# ESP32.net
KiCad netlist of a schematic drawn in EAGLE
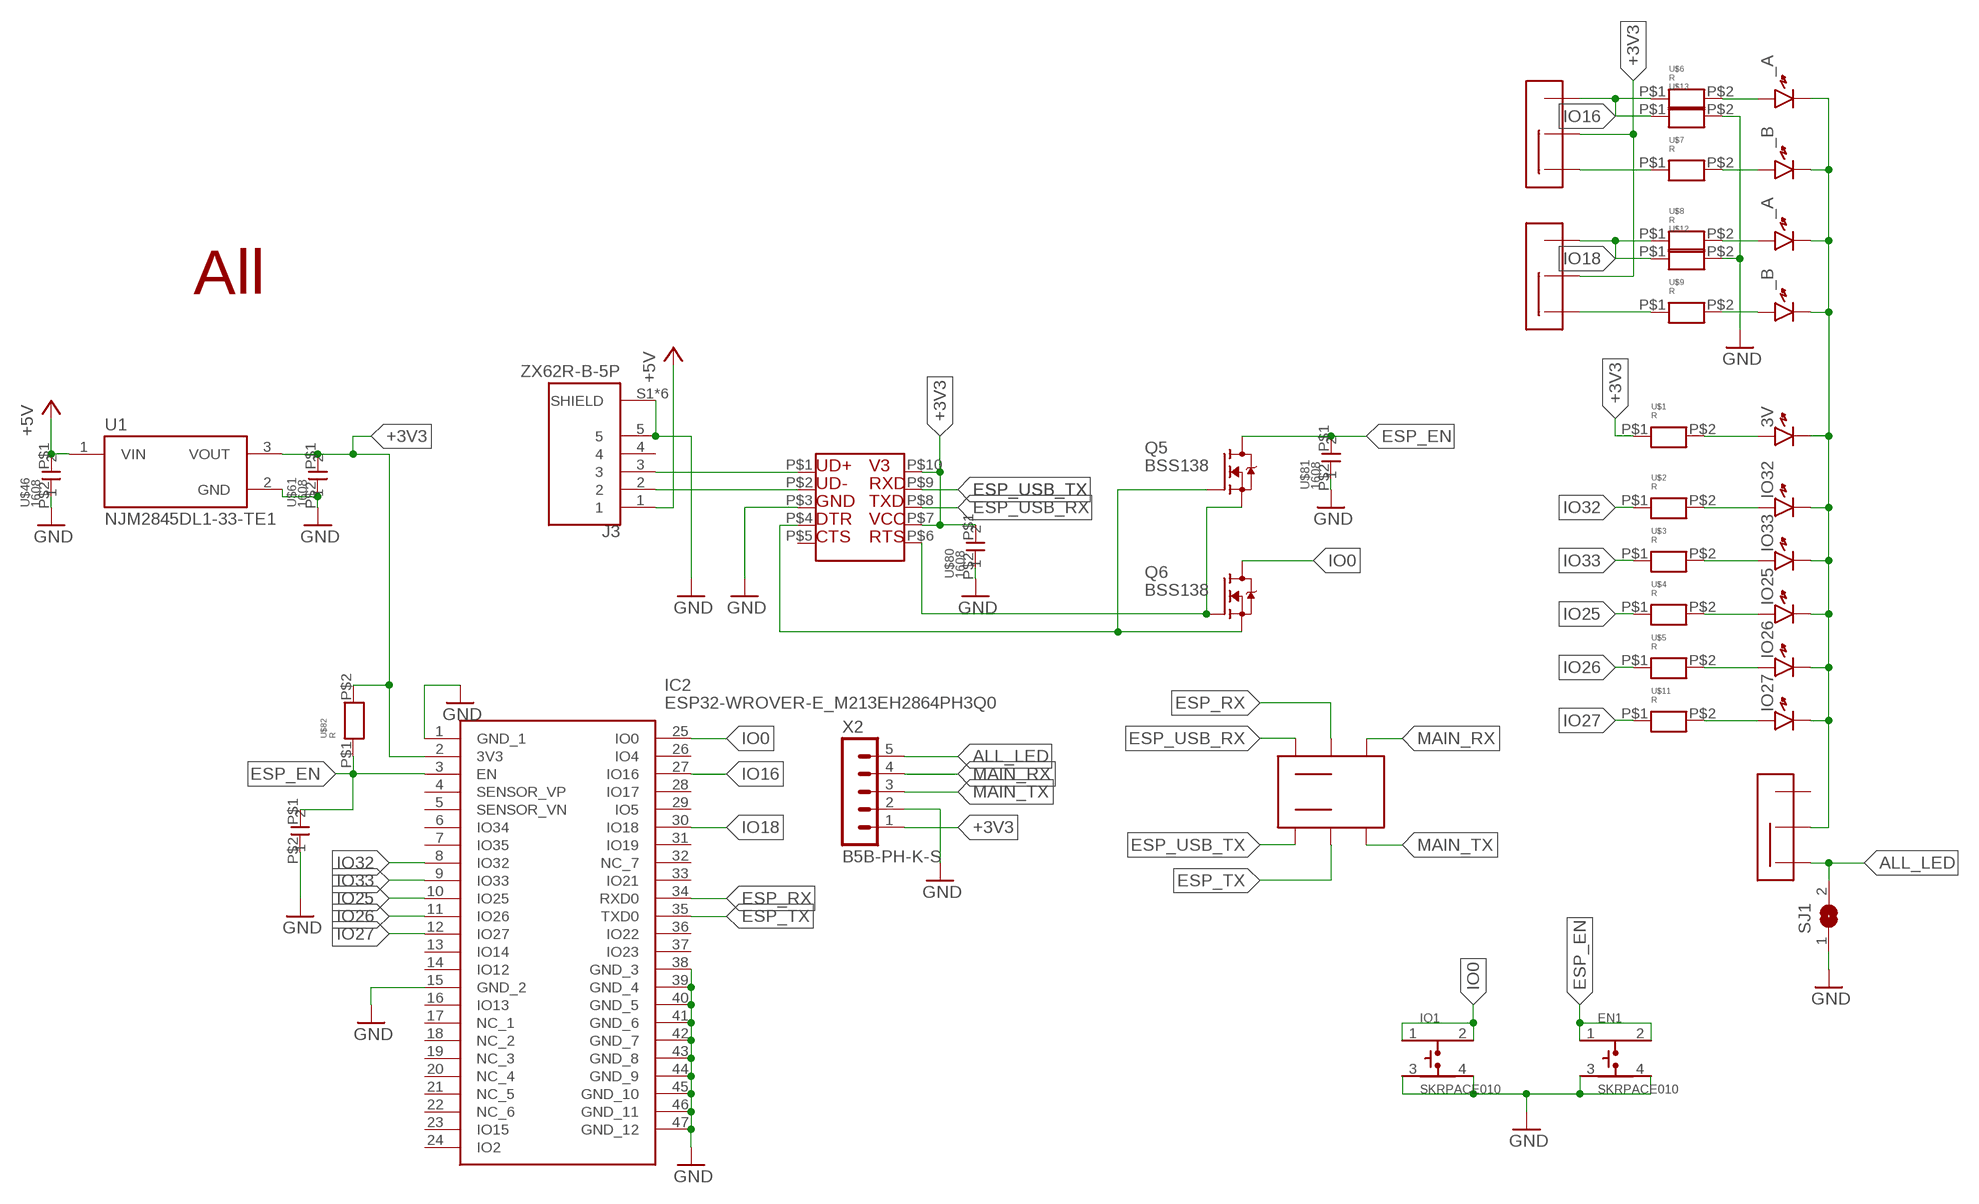
[diagram p0: schematic, sheet 1]

(export (version "E")
  (design (tool "Eeschema 10.0.6"))
  (components
    (comp (ref "3V")
      (value "LED1608")
      (footprint "eagle-import:LED1608")
      (libsource (lib "eagle-import") (part "LED1608"))
    )
    (comp (ref "EN1")
      (value "SKRPACE010")
      (footprint "eagle-import:SW_SKRPACE010")
      (fields (field (name "MF") "ALPS"))
      (libsource (lib "eagle-import") (part "SKRPACE010"))
    )
    (comp (ref "IC2")
      (value "ESP32-WROVER-E_M213EH2864PH3Q0")
      (footprint "eagle-import:ESP32WROVEREM213EH2864PH3Q0")
      (fields
        (field (name "MANUFACTURER_PART_NUMBER") "ESP32-WROVER-E(M213EH2864PH3Q0)")
        (field (name "MOUSER_PART_NUMBER") "356-ESP32WRVE22864PC")
      )
      (libsource (lib "eagle-import") (part "ESP32-WROVER-E_M213EH2864PH3Q0"))
    )
    (comp (ref "IO1")
      (value "SKRPACE010")
      (footprint "eagle-import:SW_SKRPACE010")
      (fields (field (name "MF") "ALPS"))
      (libsource (lib "eagle-import") (part "SKRPACE010"))
    )
    (comp (ref "IO25")
      (value "LED1608")
      (footprint "eagle-import:LED1608")
      (libsource (lib "eagle-import") (part "LED1608"))
    )
    (comp (ref "IO26")
      (value "LED1608")
      (footprint "eagle-import:LED1608")
      (libsource (lib "eagle-import") (part "LED1608"))
    )
    (comp (ref "IO27")
      (value "LED1608")
      (footprint "eagle-import:LED1608")
      (libsource (lib "eagle-import") (part "LED1608"))
    )
    (comp (ref "IO32")
      (value "LED1608")
      (footprint "eagle-import:LED1608")
      (libsource (lib "eagle-import") (part "LED1608"))
    )
    (comp (ref "IO33")
      (value "LED1608")
      (footprint "eagle-import:LED1608")
      (libsource (lib "eagle-import") (part "LED1608"))
    )
    (comp (ref "J3")
      (value "ZX62R-B-5P")
      (footprint "eagle-import:HRS_ZX62R-B-5P")
      (fields (field (name "MF") "Hirose"))
      (libsource (lib "eagle-import") (part "ZX62R-B-5P"))
    )
    (comp (ref "Q5")
      (value "BSS138")
      (footprint "eagle-import:SOT23")
      (fields (field (name "MF") "Fairchild"))
      (libsource (lib "eagle-import") (part "BSS138"))
    )
    (comp (ref "Q6")
      (value "BSS138")
      (footprint "eagle-import:SOT23")
      (fields (field (name "MF") "Fairchild"))
      (libsource (lib "eagle-import") (part "BSS138"))
    )
    (comp (ref "SJ1") (value "SJ") (footprint "eagle-import:SJ") (libsource (lib "eagle-import") (part "SJ")))
    (comp (ref "U$1") (value "R") (footprint "eagle-import:1608") (libsource (lib "eagle-import") (part "R")))
    (comp (ref "U$2") (value "R") (footprint "eagle-import:1608") (libsource (lib "eagle-import") (part "R")))
    (comp (ref "U$3") (value "R") (footprint "eagle-import:1608") (libsource (lib "eagle-import") (part "R")))
    (comp (ref "U$4") (value "R") (footprint "eagle-import:1608") (libsource (lib "eagle-import") (part "R")))
    (comp (ref "U$5") (value "R") (footprint "eagle-import:1608") (libsource (lib "eagle-import") (part "R")))
    (comp (ref "U$6") (value "R") (footprint "eagle-import:1608") (libsource (lib "eagle-import") (part "R")))
    (comp (ref "U$7") (value "R") (footprint "eagle-import:1608") (libsource (lib "eagle-import") (part "R")))
    (comp (ref "U$8") (value "R") (footprint "eagle-import:1608") (libsource (lib "eagle-import") (part "R")))
    (comp (ref "U$9") (value "R") (footprint "eagle-import:1608") (libsource (lib "eagle-import") (part "R")))
    (comp (ref "U$10")
      (value "SSW")
      (footprint "eagle-import:SSW")
      (libsource (lib "eagle-import") (part "SSW"))
    )
    (comp (ref "U$11")
      (value "R")
      (footprint "eagle-import:1608")
      (libsource (lib "eagle-import") (part "R"))
    )
    (comp (ref "U$12")
      (value "R")
      (footprint "eagle-import:1608")
      (libsource (lib "eagle-import") (part "R"))
    )
    (comp (ref "U$13")
      (value "R")
      (footprint "eagle-import:1608")
      (libsource (lib "eagle-import") (part "R"))
    )
    (comp (ref "U$14")
      (value "ALL")
      (footprint "eagle-import:ALL")
      (libsource (lib "eagle-import") (part "ALL"))
    )
    (comp (ref "U$46")
      (value "1608")
      (footprint "eagle-import:CON")
      (libsource (lib "eagle-import") (part "1608"))
    )
    (comp (ref "U$61")
      (value "1608")
      (footprint "eagle-import:CON")
      (libsource (lib "eagle-import") (part "1608"))
    )
    (comp (ref "U$79")
      (value "CH340K")
      (footprint "eagle-import:CH340K")
      (libsource (lib "eagle-import") (part "CH340K"))
    )
    (comp (ref "U$80")
      (value "1608")
      (footprint "eagle-import:CON")
      (libsource (lib "eagle-import") (part "1608"))
    )
    (comp (ref "U$81")
      (value "1608")
      (footprint "eagle-import:CON")
      (libsource (lib "eagle-import") (part "1608"))
    )
    (comp (ref "U$82")
      (value "R")
      (footprint "eagle-import:1608")
      (libsource (lib "eagle-import") (part "R"))
    )
    (comp (ref "U$83")
      (value "1608")
      (footprint "eagle-import:CON")
      (libsource (lib "eagle-import") (part "1608"))
    )
    (comp (ref "U$84")
      (value "2SW")
      (footprint "eagle-import:2SW")
      (libsource (lib "eagle-import") (part "2SW"))
    )
    (comp (ref "U$89")
      (value "SSW")
      (footprint "eagle-import:SSW")
      (libsource (lib "eagle-import") (part "SSW"))
    )
    (comp (ref "U$90")
      (value "SSW")
      (footprint "eagle-import:SSW")
      (libsource (lib "eagle-import") (part "SSW"))
    )
    (comp (ref "U1")
      (value "NJM2845DL1-33-TE1")
      (footprint "eagle-import:DPAK228P968X238-4N")
      (fields (field (name "MF") "NJR Corporation/NJRC"))
      (libsource (lib "eagle-import") (part "NJM2845DL1-33-TE1"))
    )
    (comp (ref "X2")
      (value "B5B-PH-K-S")
      (footprint "eagle-import:B5B-PH-K-S")
      (libsource (lib "eagle-import") (part "B5B-PH-K-S"))
    )
    (comp (ref "Ⅰ_A")
      (value "LED1608")
      (footprint "eagle-import:LED1608")
      (libsource (lib "eagle-import") (part "LED1608"))
    )
    (comp (ref "Ⅰ_B")
      (value "LED1608")
      (footprint "eagle-import:LED1608")
      (libsource (lib "eagle-import") (part "LED1608"))
    )
    (comp (ref "Ⅱ_A")
      (value "LED1608")
      (footprint "eagle-import:LED1608")
      (libsource (lib "eagle-import") (part "LED1608"))
    )
    (comp (ref "Ⅱ_B")
      (value "LED1608")
      (footprint "eagle-import:LED1608")
      (libsource (lib "eagle-import") (part "LED1608"))
    )
  )
  (nets
    (net (code "1") (name "+3V3") (class "Default")
      (node (ref "IC2") (pin "2") (pinfunction "3V3_2") (pintype "bidirectional"))
      (node (ref "U$1") (pin "P$1") (pinfunction "P$1_P$1") (pintype "bidirectional"))
      (node (ref "U$61") (pin "P$1") (pinfunction "1_P$1") (pintype "bidirectional"))
      (node (ref "U$79") (pin "P$10") (pinfunction "P$10_P$10") (pintype "bidirectional"))
      (node (ref "U$79") (pin "P$7") (pinfunction "P$7_P$7") (pintype "bidirectional"))
      (node (ref "U$80") (pin "P$1") (pinfunction "1_P$1") (pintype "bidirectional"))
      (node (ref "U$82") (pin "P$2") (pinfunction "P$2_P$2") (pintype "bidirectional"))
      (node (ref "U$89") (pin "P$3") (pinfunction "P$2_P$3") (pintype "bidirectional"))
      (node (ref "U$90") (pin "P$3") (pinfunction "P$2_P$3") (pintype "bidirectional"))
      (node (ref "U1") (pin "3") (pinfunction "VOUT_3") (pintype "output"))
      (node (ref "X2") (pin "1") (pinfunction "1_1") (pintype "passive"))
    )
    (net (code "2") (name "+5V") (class "Default")
      (node (ref "J3") (pin "1") (pinfunction "1_1") (pintype "passive"))
      (node (ref "U$46") (pin "P$1") (pinfunction "1_P$1") (pintype "bidirectional"))
      (node (ref "U1") (pin "1") (pinfunction "VIN_1") (pintype "input"))
    )
    (net (code "3") (name "ALL_LED") (class "Default")
      (node (ref "SJ1") (pin "2") (pinfunction "2_2") (pintype "passive"))
      (node (ref "U$10") (pin "P$1") (pinfunction "P$1_P$1") (pintype "bidirectional"))
      (node (ref "X2") (pin "5") (pinfunction "5_5") (pintype "passive"))
    )
    (net (code "4") (name "ESP_EN") (class "Default")
      (node (ref "EN1") (pin "1") (pinfunction "1_1") (pintype "bidirectional"))
      (node (ref "EN1") (pin "2") (pinfunction "2_2") (pintype "bidirectional"))
      (node (ref "IC2") (pin "3") (pinfunction "EN_3") (pintype "bidirectional"))
      (node (ref "Q5") (pin "3") (pinfunction "D_3") (pintype "passive"))
      (node (ref "U$81") (pin "P$1") (pinfunction "1_P$1") (pintype "bidirectional"))
      (node (ref "U$82") (pin "P$1") (pinfunction "P$1_P$1") (pintype "bidirectional"))
      (node (ref "U$83") (pin "P$1") (pinfunction "1_P$1") (pintype "bidirectional"))
    )
    (net (code "5") (name "ESP_RX") (class "Default")
      (node (ref "IC2") (pin "34") (pinfunction "RXD0_34") (pintype "bidirectional"))
      (node (ref "U$84") (pin "P$2") (pinfunction "P$2_P$2") (pintype "bidirectional"))
    )
    (net (code "6") (name "ESP_TX") (class "Default")
      (node (ref "IC2") (pin "35") (pinfunction "TXD0_35") (pintype "bidirectional"))
      (node (ref "U$84") (pin "P$5") (pinfunction "P$5_P$5") (pintype "bidirectional"))
    )
    (net (code "7") (name "ESP_USB_RX") (class "Default")
      (node (ref "U$79") (pin "P$8") (pinfunction "P$8_P$8") (pintype "bidirectional"))
      (node (ref "U$84") (pin "P$1") (pinfunction "P$1_P$1") (pintype "bidirectional"))
    )
    (net (code "8") (name "ESP_USB_TX") (class "Default")
      (node (ref "U$79") (pin "P$9") (pinfunction "P$9_P$9") (pintype "bidirectional"))
      (node (ref "U$84") (pin "P$6") (pinfunction "P$4_P$6") (pintype "bidirectional"))
    )
    (net (code "9") (name "GND") (class "Default")
      (node (ref "EN1") (pin "3") (pinfunction "3_3") (pintype "bidirectional"))
      (node (ref "EN1") (pin "4") (pinfunction "4_4") (pintype "bidirectional"))
      (node (ref "IC2") (pin "1") (pinfunction "GND_1_1") (pintype "bidirectional"))
      (node (ref "IC2") (pin "15") (pinfunction "GND_2_15") (pintype "bidirectional"))
      (node (ref "IC2") (pin "38") (pinfunction "GND_3_38") (pintype "bidirectional"))
      (node (ref "IC2") (pin "39") (pinfunction "GND_4_39") (pintype "bidirectional"))
      (node (ref "IC2") (pin "40") (pinfunction "GND_5_40") (pintype "bidirectional"))
      (node (ref "IC2") (pin "41") (pinfunction "GND_6_41") (pintype "bidirectional"))
      (node (ref "IC2") (pin "42") (pinfunction "GND_7_42") (pintype "bidirectional"))
      (node (ref "IC2") (pin "43") (pinfunction "GND_8_43") (pintype "bidirectional"))
      (node (ref "IC2") (pin "44") (pinfunction "GND_9_44") (pintype "bidirectional"))
      (node (ref "IC2") (pin "45") (pinfunction "GND_10_45") (pintype "bidirectional"))
      (node (ref "IC2") (pin "46") (pinfunction "GND_11_46") (pintype "bidirectional"))
      (node (ref "IC2") (pin "47") (pinfunction "GND_12_47") (pintype "bidirectional"))
      (node (ref "IO1") (pin "3") (pinfunction "3_3") (pintype "bidirectional"))
      (node (ref "IO1") (pin "4") (pinfunction "4_4") (pintype "bidirectional"))
      (node (ref "J3") (pin "5") (pinfunction "5_5") (pintype "passive"))
      (node (ref "J3") (pin "S1") (pinfunction "SHIELD_S1") (pintype "passive"))
      (node (ref "J3") (pin "S2") (pinfunction "SHIELD_S2") (pintype "passive"))
      (node (ref "J3") (pin "S3") (pinfunction "SHIELD_S3") (pintype "passive"))
      (node (ref "J3") (pin "S4") (pinfunction "SHIELD_S4") (pintype "passive"))
      (node (ref "J3") (pin "S5") (pinfunction "SHIELD_S5") (pintype "passive"))
      (node (ref "J3") (pin "S6") (pinfunction "SHIELD_S6") (pintype "passive"))
      (node (ref "SJ1") (pin "1") (pinfunction "1_1") (pintype "passive"))
      (node (ref "U$12") (pin "P$2") (pinfunction "P$2_P$2") (pintype "bidirectional"))
      (node (ref "U$13") (pin "P$2") (pinfunction "P$2_P$2") (pintype "bidirectional"))
      (node (ref "U$46") (pin "P$2") (pinfunction "2_P$2") (pintype "bidirectional"))
      (node (ref "U$61") (pin "P$2") (pinfunction "2_P$2") (pintype "bidirectional"))
      (node (ref "U$79") (pin "P$3") (pinfunction "P$3_P$3") (pintype "bidirectional"))
      (node (ref "U$80") (pin "P$2") (pinfunction "2_P$2") (pintype "bidirectional"))
      (node (ref "U$81") (pin "P$2") (pinfunction "2_P$2") (pintype "bidirectional"))
      (node (ref "U$83") (pin "P$2") (pinfunction "2_P$2") (pintype "bidirectional"))
      (node (ref "U1") (pin "2") (pinfunction "GND_2") (pintype "power_in"))
      (node (ref "X2") (pin "2") (pinfunction "2_2") (pintype "passive"))
    )
    (net (code "10") (name "IO0") (class "Default")
      (node (ref "IC2") (pin "25") (pinfunction "IO0_25") (pintype "bidirectional"))
      (node (ref "IO1") (pin "1") (pinfunction "1_1") (pintype "bidirectional"))
      (node (ref "IO1") (pin "2") (pinfunction "2_2") (pintype "bidirectional"))
      (node (ref "Q6") (pin "3") (pinfunction "D_3") (pintype "passive"))
    )
    (net (code "11") (name "IO16") (class "Default")
      (node (ref "IC2") (pin "27") (pinfunction "IO16_27") (pintype "bidirectional"))
      (node (ref "U$13") (pin "P$1") (pinfunction "P$1_P$1") (pintype "bidirectional"))
      (node (ref "U$6") (pin "P$1") (pinfunction "P$1_P$1") (pintype "bidirectional"))
      (node (ref "U$89") (pin "P$2") (pinfunction "P$3_P$2") (pintype "bidirectional"))
    )
    (net (code "12") (name "IO18") (class "Default")
      (node (ref "IC2") (pin "30") (pinfunction "IO18_30") (pintype "bidirectional"))
      (node (ref "U$12") (pin "P$1") (pinfunction "P$1_P$1") (pintype "bidirectional"))
      (node (ref "U$8") (pin "P$1") (pinfunction "P$1_P$1") (pintype "bidirectional"))
      (node (ref "U$90") (pin "P$2") (pinfunction "P$3_P$2") (pintype "bidirectional"))
    )
    (net (code "13") (name "IO25") (class "Default")
      (node (ref "IC2") (pin "10") (pinfunction "IO25_10") (pintype "bidirectional"))
      (node (ref "U$4") (pin "P$1") (pinfunction "P$1_P$1") (pintype "bidirectional"))
    )
    (net (code "14") (name "IO26") (class "Default")
      (node (ref "IC2") (pin "11") (pinfunction "IO26_11") (pintype "bidirectional"))
      (node (ref "U$5") (pin "P$1") (pinfunction "P$1_P$1") (pintype "bidirectional"))
    )
    (net (code "15") (name "IO27") (class "Default")
      (node (ref "IC2") (pin "12") (pinfunction "IO27_12") (pintype "bidirectional"))
      (node (ref "U$11") (pin "P$1") (pinfunction "P$1_P$1") (pintype "bidirectional"))
    )
    (net (code "16") (name "IO32") (class "Default")
      (node (ref "IC2") (pin "8") (pinfunction "IO32_8") (pintype "bidirectional"))
      (node (ref "U$2") (pin "P$1") (pinfunction "P$1_P$1") (pintype "bidirectional"))
    )
    (net (code "17") (name "IO33") (class "Default")
      (node (ref "IC2") (pin "9") (pinfunction "IO33_9") (pintype "bidirectional"))
      (node (ref "U$3") (pin "P$1") (pinfunction "P$1_P$1") (pintype "bidirectional"))
    )
    (net (code "18") (name "MAIN_RX") (class "Default")
      (node (ref "U$84") (pin "P$3") (pinfunction "P$3_P$3") (pintype "bidirectional"))
      (node (ref "X2") (pin "4") (pinfunction "4_4") (pintype "passive"))
    )
    (net (code "19") (name "MAIN_TX") (class "Default")
      (node (ref "U$84") (pin "P$4") (pinfunction "P$6_P$4") (pintype "bidirectional"))
      (node (ref "X2") (pin "3") (pinfunction "3_3") (pintype "passive"))
    )
    (net (code "20") (name "Net-(3V-PadA)") (class "Default")
      (node (ref "3V") (pin "A") (pinfunction "A_A") (pintype "passive"))
      (node (ref "U$1") (pin "P$2") (pinfunction "P$2_P$2") (pintype "bidirectional"))
    )
    (net (code "21") (name "Net-(IO25-PadA)") (class "Default")
      (node (ref "IO25") (pin "A") (pinfunction "A_A") (pintype "passive"))
      (node (ref "U$4") (pin "P$2") (pinfunction "P$2_P$2") (pintype "bidirectional"))
    )
    (net (code "22") (name "Net-(IO26-PadA)") (class "Default")
      (node (ref "IO26") (pin "A") (pinfunction "A_A") (pintype "passive"))
      (node (ref "U$5") (pin "P$2") (pinfunction "P$2_P$2") (pintype "bidirectional"))
    )
    (net (code "23") (name "Net-(IO27-PadA)") (class "Default")
      (node (ref "IO27") (pin "A") (pinfunction "A_A") (pintype "passive"))
      (node (ref "U$11") (pin "P$2") (pinfunction "P$2_P$2") (pintype "bidirectional"))
    )
    (net (code "24") (name "Net-(IO32-PadA)") (class "Default")
      (node (ref "IO32") (pin "A") (pinfunction "A_A") (pintype "passive"))
      (node (ref "U$2") (pin "P$2") (pinfunction "P$2_P$2") (pintype "bidirectional"))
    )
    (net (code "25") (name "Net-(IO33-PadA)") (class "Default")
      (node (ref "IO33") (pin "A") (pinfunction "A_A") (pintype "passive"))
      (node (ref "U$3") (pin "P$2") (pinfunction "P$2_P$2") (pintype "bidirectional"))
    )
    (net (code "26") (name "Net-(J3-Pad2)") (class "Default")
      (node (ref "J3") (pin "2") (pinfunction "2_2") (pintype "passive"))
      (node (ref "U$79") (pin "P$2") (pinfunction "P$2_P$2") (pintype "bidirectional"))
    )
    (net (code "27") (name "Net-(J3-Pad3)") (class "Default")
      (node (ref "J3") (pin "3") (pinfunction "3_3") (pintype "passive"))
      (node (ref "U$79") (pin "P$1") (pinfunction "P$1_P$1") (pintype "bidirectional"))
    )
    (net (code "28") (name "Net-(Q5-G)") (class "Default")
      (node (ref "Q5") (pin "1") (pinfunction "G_1") (pintype "passive"))
      (node (ref "Q6") (pin "2") (pinfunction "S_2") (pintype "passive"))
      (node (ref "U$79") (pin "P$4") (pinfunction "P$4_P$4") (pintype "bidirectional"))
    )
    (net (code "29") (name "Net-(Q5-S)") (class "Default")
      (node (ref "Q5") (pin "2") (pinfunction "S_2") (pintype "passive"))
      (node (ref "Q6") (pin "1") (pinfunction "G_1") (pintype "passive"))
      (node (ref "U$79") (pin "P$6") (pinfunction "P$6_P$6") (pintype "bidirectional"))
    )
    (net (code "30") (name "Net-(U$6-PadP$2)") (class "Default")
      (node (ref "U$6") (pin "P$2") (pinfunction "P$2_P$2") (pintype "bidirectional"))
      (node (ref "Ⅰ_A") (pin "A") (pinfunction "A_A") (pintype "passive"))
    )
    (net (code "31") (name "Net-(U$7-PadP$1)") (class "Default")
      (node (ref "U$7") (pin "P$1") (pinfunction "P$1_P$1") (pintype "bidirectional"))
      (node (ref "U$89") (pin "P$1") (pinfunction "P$1_P$1") (pintype "bidirectional"))
    )
    (net (code "32") (name "Net-(U$7-PadP$2)") (class "Default")
      (node (ref "U$7") (pin "P$2") (pinfunction "P$2_P$2") (pintype "bidirectional"))
      (node (ref "Ⅰ_B") (pin "A") (pinfunction "A_A") (pintype "passive"))
    )
    (net (code "33") (name "Net-(U$8-PadP$2)") (class "Default")
      (node (ref "U$8") (pin "P$2") (pinfunction "P$2_P$2") (pintype "bidirectional"))
      (node (ref "Ⅱ_A") (pin "A") (pinfunction "A_A") (pintype "passive"))
    )
    (net (code "34") (name "Net-(U$9-PadP$1)") (class "Default")
      (node (ref "U$9") (pin "P$1") (pinfunction "P$1_P$1") (pintype "bidirectional"))
      (node (ref "U$90") (pin "P$1") (pinfunction "P$1_P$1") (pintype "bidirectional"))
    )
    (net (code "35") (name "Net-(U$9-PadP$2)") (class "Default")
      (node (ref "U$9") (pin "P$2") (pinfunction "P$2_P$2") (pintype "bidirectional"))
      (node (ref "Ⅱ_B") (pin "A") (pinfunction "A_A") (pintype "passive"))
    )
    (net (code "36") (name "Net-(U$10-P$2)") (class "Default")
      (node (ref "3V") (pin "K") (pinfunction "K_K") (pintype "passive"))
      (node (ref "IO25") (pin "K") (pinfunction "K_K") (pintype "passive"))
      (node (ref "IO26") (pin "K") (pinfunction "K_K") (pintype "passive"))
      (node (ref "IO27") (pin "K") (pinfunction "K_K") (pintype "passive"))
      (node (ref "IO32") (pin "K") (pinfunction "K_K") (pintype "passive"))
      (node (ref "IO33") (pin "K") (pinfunction "K_K") (pintype "passive"))
      (node (ref "U$10") (pin "P$3") (pinfunction "P$2_P$3") (pintype "bidirectional"))
      (node (ref "Ⅰ_A") (pin "K") (pinfunction "K_K") (pintype "passive"))
      (node (ref "Ⅰ_B") (pin "K") (pinfunction "K_K") (pintype "passive"))
      (node (ref "Ⅱ_A") (pin "K") (pinfunction "K_K") (pintype "passive"))
      (node (ref "Ⅱ_B") (pin "K") (pinfunction "K_K") (pintype "passive"))
    )
    (net (code "37") (name "unconnected-(IC2-IO2-Pad24)") (class "Default")
      (node (ref "IC2") (pin "24") (pinfunction "IO2_24") (pintype "bidirectional"))
    )
    (net (code "38") (name "unconnected-(IC2-IO4-Pad26)") (class "Default")
      (node (ref "IC2") (pin "26") (pinfunction "IO4_26") (pintype "bidirectional"))
    )
    (net (code "39") (name "unconnected-(IC2-IO5-Pad29)") (class "Default")
      (node (ref "IC2") (pin "29") (pinfunction "IO5_29") (pintype "bidirectional"))
    )
    (net (code "40") (name "unconnected-(IC2-IO12-Pad14)") (class "Default")
      (node (ref "IC2") (pin "14") (pinfunction "IO12_14") (pintype "bidirectional"))
    )
    (net (code "41") (name "unconnected-(IC2-IO13-Pad16)") (class "Default")
      (node (ref "IC2") (pin "16") (pinfunction "IO13_16") (pintype "bidirectional"))
    )
    (net (code "42") (name "unconnected-(IC2-IO14-Pad13)") (class "Default")
      (node (ref "IC2") (pin "13") (pinfunction "IO14_13") (pintype "bidirectional"))
    )
    (net (code "43") (name "unconnected-(IC2-IO15-Pad23)") (class "Default")
      (node (ref "IC2") (pin "23") (pinfunction "IO15_23") (pintype "bidirectional"))
    )
    (net (code "44") (name "unconnected-(IC2-IO17-Pad28)") (class "Default")
      (node (ref "IC2") (pin "28") (pinfunction "IO17_28") (pintype "bidirectional"))
    )
    (net (code "45") (name "unconnected-(IC2-IO19-Pad31)") (class "Default")
      (node (ref "IC2") (pin "31") (pinfunction "IO19_31") (pintype "bidirectional"))
    )
    (net (code "46") (name "unconnected-(IC2-IO21-Pad33)") (class "Default")
      (node (ref "IC2") (pin "33") (pinfunction "IO21_33") (pintype "bidirectional"))
    )
    (net (code "47") (name "unconnected-(IC2-IO22-Pad36)") (class "Default")
      (node (ref "IC2") (pin "36") (pinfunction "IO22_36") (pintype "bidirectional"))
    )
    (net (code "48") (name "unconnected-(IC2-IO23-Pad37)") (class "Default")
      (node (ref "IC2") (pin "37") (pinfunction "IO23_37") (pintype "bidirectional"))
    )
    (net (code "49") (name "unconnected-(IC2-IO34-Pad6)") (class "Default")
      (node (ref "IC2") (pin "6") (pinfunction "IO34_6") (pintype "bidirectional"))
    )
    (net (code "50") (name "unconnected-(IC2-IO35-Pad7)") (class "Default")
      (node (ref "IC2") (pin "7") (pinfunction "IO35_7") (pintype "bidirectional"))
    )
    (net (code "51") (name "unconnected-(IC2-NC_1-Pad17)") (class "Default")
      (node (ref "IC2") (pin "17") (pinfunction "NC_1_17") (pintype "bidirectional"))
    )
    (net (code "52") (name "unconnected-(IC2-NC_2-Pad18)") (class "Default")
      (node (ref "IC2") (pin "18") (pinfunction "NC_2_18") (pintype "bidirectional"))
    )
    (net (code "53") (name "unconnected-(IC2-NC_3-Pad19)") (class "Default")
      (node (ref "IC2") (pin "19") (pinfunction "NC_3_19") (pintype "bidirectional"))
    )
    (net (code "54") (name "unconnected-(IC2-NC_4-Pad20)") (class "Default")
      (node (ref "IC2") (pin "20") (pinfunction "NC_4_20") (pintype "bidirectional"))
    )
    (net (code "55") (name "unconnected-(IC2-NC_5-Pad21)") (class "Default")
      (node (ref "IC2") (pin "21") (pinfunction "NC_5_21") (pintype "bidirectional"))
    )
    (net (code "56") (name "unconnected-(IC2-NC_6-Pad22)") (class "Default")
      (node (ref "IC2") (pin "22") (pinfunction "NC_6_22") (pintype "bidirectional"))
    )
    (net (code "57") (name "unconnected-(IC2-NC_7-Pad32)") (class "Default")
      (node (ref "IC2") (pin "32") (pinfunction "NC_7_32") (pintype "bidirectional"))
    )
    (net (code "58") (name "unconnected-(IC2-SENSOR_VN-Pad5)") (class "Default")
      (node (ref "IC2") (pin "5") (pinfunction "SENSOR_VN_5") (pintype "bidirectional"))
    )
    (net (code "59") (name "unconnected-(IC2-SENSOR_VP-Pad4)") (class "Default")
      (node (ref "IC2") (pin "4") (pinfunction "SENSOR_VP_4") (pintype "bidirectional"))
    )
    (net (code "60") (name "unconnected-(J3-Pad4)") (class "Default")
      (node (ref "J3") (pin "4") (pinfunction "4_4") (pintype "passive"))
    )
    (net (code "61") (name "unconnected-(U$10-P$3-PadP$2)") (class "Default")
      (node (ref "U$10") (pin "P$2") (pinfunction "P$3_P$2") (pintype "bidirectional"))
    )
    (net (code "62") (name "unconnected-(U$79-PadP$5)") (class "Default")
      (node (ref "U$79") (pin "P$5") (pinfunction "P$5_P$5") (pintype "bidirectional"))
    )
  )
)
